# placa3.net
KiCad netlist of a schematic drawn in EAGLE
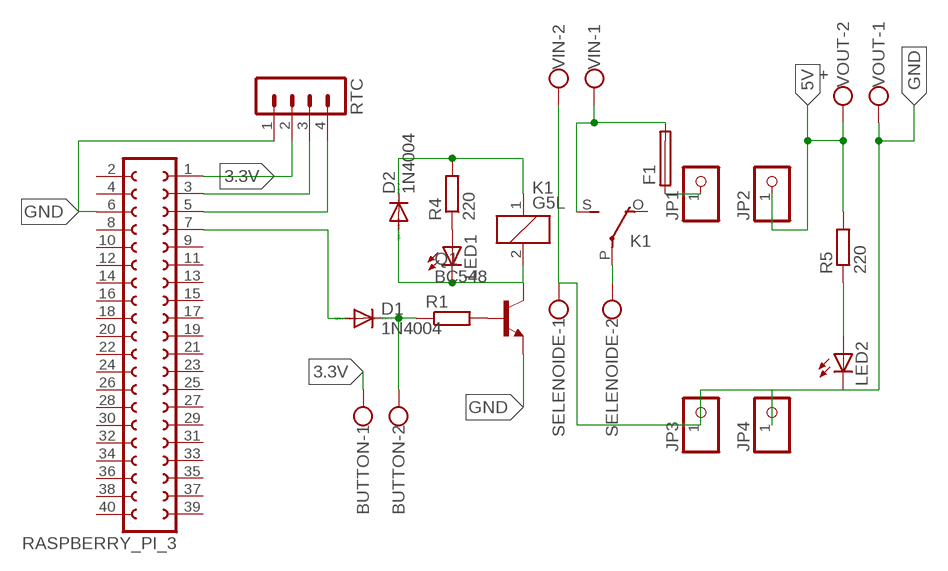
[diagram p0: schematic, sheet 1]

(export (version "E")
  (design (tool "Eeschema 10.0.6"))
  (components
    (comp (ref "BUTTON")
      (value "W237-102")
      (footprint "eagle-import:W237-102")
      (fields (field (name "MPN") "237-102"))
      (libsource (lib "eagle-import") (part "W237-102"))
    )
    (comp (ref "D1")
      (value "1N4004")
      (footprint "eagle-import:DO41-10")
      (libsource (lib "eagle-import") (part "1N4004"))
    )
    (comp (ref "D2")
      (value "1N4004")
      (footprint "eagle-import:DO41-10")
      (libsource (lib "eagle-import") (part "1N4004"))
    )
    (comp (ref "F1")
      (value "SH22,5")
      (footprint "eagle-import:SH22,5")
      (fields (field (name "MF") "SCHURTER") (field (name "MPN") "0031.8201"))
      (libsource (lib "eagle-import") (part "SH22,5"))
    )
    (comp (ref "JP1")
      (value "PINHD-1X1")
      (footprint "eagle-import:1X01")
      (libsource (lib "eagle-import") (part "PINHD-1X1"))
    )
    (comp (ref "JP2")
      (value "PINHD-1X1")
      (footprint "eagle-import:1X01")
      (libsource (lib "eagle-import") (part "PINHD-1X1"))
    )
    (comp (ref "JP3")
      (value "PINHD-1X1")
      (footprint "eagle-import:1X01")
      (libsource (lib "eagle-import") (part "PINHD-1X1"))
    )
    (comp (ref "JP4")
      (value "PINHD-1X1")
      (footprint "eagle-import:1X01")
      (libsource (lib "eagle-import") (part "PINHD-1X1"))
    )
    (comp (ref "K1")
      (value "G5L")
      (footprint "eagle-import:G5LE")
      (libsource (lib "eagle-import") (part "G5L"))
    )
    (comp (ref "LED1")
      (value "LED5MM")
      (footprint "eagle-import:LED5MM")
      (libsource (lib "eagle-import") (part "LED5MM"))
    )
    (comp (ref "LED2")
      (value "LED5MM")
      (footprint "eagle-import:LED5MM")
      (libsource (lib "eagle-import") (part "LED5MM"))
    )
    (comp (ref "Q1")
      (value "BC548")
      (footprint "eagle-import:TO92-EBC")
      (libsource (lib "eagle-import") (part "BC548"))
    )
    (comp (ref "R1")
      (value "R-EU_0204/7")
      (footprint "eagle-import:0204_7")
      (libsource (lib "eagle-import") (part "R-EU_0204/7"))
    )
    (comp (ref "R4")
      (value "220")
      (footprint "eagle-import:0204_7")
      (libsource (lib "eagle-import") (part "R-EU_0204/7"))
    )
    (comp (ref "R5")
      (value "220")
      (footprint "eagle-import:0204_7")
      (libsource (lib "eagle-import") (part "R-EU_0204/7"))
    )
    (comp (ref "RASPBERRY_PI_3")
      (value "FE20-2")
      (footprint "eagle-import:FE20-2")
      (libsource (lib "eagle-import") (part "FE20-2"))
    )
    (comp (ref "RTC")
      (value "MA04-1")
      (footprint "eagle-import:MA04-1")
      (libsource (lib "eagle-import") (part "MA04-1"))
    )
    (comp (ref "SELENOIDE")
      (value "W237-102")
      (footprint "eagle-import:W237-102")
      (fields (field (name "MPN") "237-102"))
      (libsource (lib "eagle-import") (part "W237-102"))
    )
    (comp (ref "VIN")
      (value "W237-102")
      (footprint "eagle-import:W237-102")
      (fields (field (name "MPN") "237-102"))
      (libsource (lib "eagle-import") (part "W237-102"))
    )
    (comp (ref "VOUT")
      (value "+")
      (footprint "eagle-import:W237-102")
      (fields (field (name "MPN") "237-102"))
      (libsource (lib "eagle-import") (part "W237-102"))
    )
  )
  (nets
    (net (code "1") (name "3.3V") (class "Default")
      (node (ref "BUTTON") (pin "1") (pinfunction "KL_1") (pintype "passive"))
      (node (ref "RASPBERRY_PI_3") (pin "1") (pinfunction "1_1") (pintype "passive"))
      (node (ref "RTC") (pin "2") (pinfunction "2_2") (pintype "passive"))
    )
    (net (code "2") (name "5V") (class "Default")
      (node (ref "D2") (pin "C") (pinfunction "C_C") (pintype "passive"))
      (node (ref "JP2") (pin "1") (pinfunction "1_1") (pintype "passive"))
      (node (ref "K1") (pin "1") (pinfunction "1_1") (pintype "passive"))
      (node (ref "R4") (pin "2") (pinfunction "2_2") (pintype "passive"))
      (node (ref "R5") (pin "2") (pinfunction "2_2") (pintype "passive"))
      (node (ref "VOUT") (pin "2") (pinfunction "KL_2") (pintype "passive"))
    )
    (net (code "3") (name "GND") (class "Default")
      (node (ref "JP3") (pin "1") (pinfunction "1_1") (pintype "passive"))
      (node (ref "JP4") (pin "1") (pinfunction "1_1") (pintype "passive"))
      (node (ref "LED2") (pin "K") (pinfunction "C_K") (pintype "passive"))
      (node (ref "Q1") (pin "E") (pinfunction "E_E") (pintype "passive"))
      (node (ref "RASPBERRY_PI_3") (pin "6") (pinfunction "6_6") (pintype "passive"))
      (node (ref "RTC") (pin "1") (pinfunction "1_1") (pintype "passive"))
      (node (ref "SELENOIDE") (pin "1") (pinfunction "KL_1") (pintype "passive"))
      (node (ref "VIN") (pin "2") (pinfunction "KL_2") (pintype "passive"))
      (node (ref "VOUT") (pin "1") (pinfunction "KL_1") (pintype "passive"))
    )
    (net (code "4") (name "Net-(BUTTONB-KL)") (class "Default")
      (node (ref "BUTTON") (pin "2") (pinfunction "KL_2") (pintype "passive"))
      (node (ref "D1") (pin "C") (pinfunction "C_C") (pintype "passive"))
      (node (ref "R1") (pin "1") (pinfunction "1_1") (pintype "passive"))
    )
    (net (code "5") (name "Net-(D1-PadA)") (class "Default")
      (node (ref "D1") (pin "A") (pinfunction "A_A") (pintype "passive"))
      (node (ref "RASPBERRY_PI_3") (pin "7") (pinfunction "7_7") (pintype "passive"))
    )
    (net (code "6") (name "Net-(F1-Pad1)") (class "Default")
      (node (ref "F1") (pin "1") (pinfunction "1_1") (pintype "passive"))
      (node (ref "JP1") (pin "1") (pinfunction "1_1") (pintype "passive"))
    )
    (net (code "7") (name "Net-(LED1-C)") (class "Default")
      (node (ref "D2") (pin "A") (pinfunction "A_A") (pintype "passive"))
      (node (ref "K1") (pin "2") (pinfunction "2_2") (pintype "passive"))
      (node (ref "LED1") (pin "K") (pinfunction "C_K") (pintype "passive"))
      (node (ref "Q1") (pin "C") (pinfunction "C_C") (pintype "passive"))
    )
    (net (code "8") (name "Net-(LED1-PadA)") (class "Default")
      (node (ref "LED1") (pin "A") (pinfunction "A_A") (pintype "passive"))
      (node (ref "R4") (pin "1") (pinfunction "1_1") (pintype "passive"))
    )
    (net (code "9") (name "Net-(LED2-PadA)") (class "Default")
      (node (ref "LED2") (pin "A") (pinfunction "A_A") (pintype "passive"))
      (node (ref "R5") (pin "1") (pinfunction "1_1") (pintype "passive"))
    )
    (net (code "10") (name "Net-(Q1-PadB)") (class "Default")
      (node (ref "Q1") (pin "B") (pinfunction "B_B") (pintype "passive"))
      (node (ref "R1") (pin "2") (pinfunction "2_2") (pintype "passive"))
    )
    (net (code "11") (name "Net-(RASPBERRY_PI_3-Pad3)") (class "Default")
      (node (ref "RASPBERRY_PI_3") (pin "3") (pinfunction "3_3") (pintype "passive"))
      (node (ref "RTC") (pin "3") (pinfunction "3_3") (pintype "passive"))
    )
    (net (code "12") (name "Net-(RASPBERRY_PI_3-Pad5)") (class "Default")
      (node (ref "RASPBERRY_PI_3") (pin "5") (pinfunction "5_5") (pintype "passive"))
      (node (ref "RTC") (pin "4") (pinfunction "4_4") (pintype "passive"))
    )
    (net (code "13") (name "Net-(SELENOIDEB-KL)") (class "Default")
      (node (ref "K1") (pin "P") (pinfunction "P_P") (pintype "passive"))
      (node (ref "SELENOIDE") (pin "2") (pinfunction "KL_2") (pintype "passive"))
    )
    (net (code "14") (name "Net-(VINA-KL)") (class "Default")
      (node (ref "F1") (pin "2") (pinfunction "2_2") (pintype "passive"))
      (node (ref "K1") (pin "S") (pinfunction "S_S") (pintype "passive"))
      (node (ref "VIN") (pin "1") (pinfunction "KL_1") (pintype "passive"))
    )
    (net (code "15") (name "unconnected-(K1-PadO)") (class "Default")
      (node (ref "K1") (pin "O") (pinfunction "O_O") (pintype "passive"))
    )
    (net (code "16") (name "unconnected-(RASPBERRY_PI_3-Pad2)") (class "Default")
      (node (ref "RASPBERRY_PI_3") (pin "2") (pinfunction "2_2") (pintype "passive"))
    )
    (net (code "17") (name "unconnected-(RASPBERRY_PI_3-Pad4)") (class "Default")
      (node (ref "RASPBERRY_PI_3") (pin "4") (pinfunction "4_4") (pintype "passive"))
    )
    (net (code "18") (name "unconnected-(RASPBERRY_PI_3-Pad8)") (class "Default")
      (node (ref "RASPBERRY_PI_3") (pin "8") (pinfunction "8_8") (pintype "passive"))
    )
    (net (code "19") (name "unconnected-(RASPBERRY_PI_3-Pad9)") (class "Default")
      (node (ref "RASPBERRY_PI_3") (pin "9") (pinfunction "9_9") (pintype "passive"))
    )
    (net (code "20") (name "unconnected-(RASPBERRY_PI_3-Pad10)") (class "Default")
      (node (ref "RASPBERRY_PI_3") (pin "10") (pinfunction "10_10") (pintype "passive"))
    )
    (net (code "21") (name "unconnected-(RASPBERRY_PI_3-Pad11)") (class "Default")
      (node (ref "RASPBERRY_PI_3") (pin "11") (pinfunction "11_11") (pintype "passive"))
    )
    (net (code "22") (name "unconnected-(RASPBERRY_PI_3-Pad12)") (class "Default")
      (node (ref "RASPBERRY_PI_3") (pin "12") (pinfunction "12_12") (pintype "passive"))
    )
    (net (code "23") (name "unconnected-(RASPBERRY_PI_3-Pad13)") (class "Default")
      (node (ref "RASPBERRY_PI_3") (pin "13") (pinfunction "13_13") (pintype "passive"))
    )
    (net (code "24") (name "unconnected-(RASPBERRY_PI_3-Pad14)") (class "Default")
      (node (ref "RASPBERRY_PI_3") (pin "14") (pinfunction "14_14") (pintype "passive"))
    )
    (net (code "25") (name "unconnected-(RASPBERRY_PI_3-Pad15)") (class "Default")
      (node (ref "RASPBERRY_PI_3") (pin "15") (pinfunction "15_15") (pintype "passive"))
    )
    (net (code "26") (name "unconnected-(RASPBERRY_PI_3-Pad16)") (class "Default")
      (node (ref "RASPBERRY_PI_3") (pin "16") (pinfunction "16_16") (pintype "passive"))
    )
    (net (code "27") (name "unconnected-(RASPBERRY_PI_3-Pad17)") (class "Default")
      (node (ref "RASPBERRY_PI_3") (pin "17") (pinfunction "17_17") (pintype "passive"))
    )
    (net (code "28") (name "unconnected-(RASPBERRY_PI_3-Pad18)") (class "Default")
      (node (ref "RASPBERRY_PI_3") (pin "18") (pinfunction "18_18") (pintype "passive"))
    )
    (net (code "29") (name "unconnected-(RASPBERRY_PI_3-Pad19)") (class "Default")
      (node (ref "RASPBERRY_PI_3") (pin "19") (pinfunction "19_19") (pintype "passive"))
    )
    (net (code "30") (name "unconnected-(RASPBERRY_PI_3-Pad20)") (class "Default")
      (node (ref "RASPBERRY_PI_3") (pin "20") (pinfunction "20_20") (pintype "passive"))
    )
    (net (code "31") (name "unconnected-(RASPBERRY_PI_3-Pad21)") (class "Default")
      (node (ref "RASPBERRY_PI_3") (pin "21") (pinfunction "21_21") (pintype "passive"))
    )
    (net (code "32") (name "unconnected-(RASPBERRY_PI_3-Pad22)") (class "Default")
      (node (ref "RASPBERRY_PI_3") (pin "22") (pinfunction "22_22") (pintype "passive"))
    )
    (net (code "33") (name "unconnected-(RASPBERRY_PI_3-Pad23)") (class "Default")
      (node (ref "RASPBERRY_PI_3") (pin "23") (pinfunction "23_23") (pintype "passive"))
    )
    (net (code "34") (name "unconnected-(RASPBERRY_PI_3-Pad24)") (class "Default")
      (node (ref "RASPBERRY_PI_3") (pin "24") (pinfunction "24_24") (pintype "passive"))
    )
    (net (code "35") (name "unconnected-(RASPBERRY_PI_3-Pad25)") (class "Default")
      (node (ref "RASPBERRY_PI_3") (pin "25") (pinfunction "25_25") (pintype "passive"))
    )
    (net (code "36") (name "unconnected-(RASPBERRY_PI_3-Pad26)") (class "Default")
      (node (ref "RASPBERRY_PI_3") (pin "26") (pinfunction "26_26") (pintype "passive"))
    )
    (net (code "37") (name "unconnected-(RASPBERRY_PI_3-Pad27)") (class "Default")
      (node (ref "RASPBERRY_PI_3") (pin "27") (pinfunction "27_27") (pintype "passive"))
    )
    (net (code "38") (name "unconnected-(RASPBERRY_PI_3-Pad28)") (class "Default")
      (node (ref "RASPBERRY_PI_3") (pin "28") (pinfunction "28_28") (pintype "passive"))
    )
    (net (code "39") (name "unconnected-(RASPBERRY_PI_3-Pad29)") (class "Default")
      (node (ref "RASPBERRY_PI_3") (pin "29") (pinfunction "29_29") (pintype "passive"))
    )
    (net (code "40") (name "unconnected-(RASPBERRY_PI_3-Pad30)") (class "Default")
      (node (ref "RASPBERRY_PI_3") (pin "30") (pinfunction "30_30") (pintype "passive"))
    )
    (net (code "41") (name "unconnected-(RASPBERRY_PI_3-Pad31)") (class "Default")
      (node (ref "RASPBERRY_PI_3") (pin "31") (pinfunction "31_31") (pintype "passive"))
    )
    (net (code "42") (name "unconnected-(RASPBERRY_PI_3-Pad32)") (class "Default")
      (node (ref "RASPBERRY_PI_3") (pin "32") (pinfunction "32_32") (pintype "passive"))
    )
    (net (code "43") (name "unconnected-(RASPBERRY_PI_3-Pad33)") (class "Default")
      (node (ref "RASPBERRY_PI_3") (pin "33") (pinfunction "33_33") (pintype "passive"))
    )
    (net (code "44") (name "unconnected-(RASPBERRY_PI_3-Pad34)") (class "Default")
      (node (ref "RASPBERRY_PI_3") (pin "34") (pinfunction "34_34") (pintype "passive"))
    )
    (net (code "45") (name "unconnected-(RASPBERRY_PI_3-Pad35)") (class "Default")
      (node (ref "RASPBERRY_PI_3") (pin "35") (pinfunction "35_35") (pintype "passive"))
    )
    (net (code "46") (name "unconnected-(RASPBERRY_PI_3-Pad36)") (class "Default")
      (node (ref "RASPBERRY_PI_3") (pin "36") (pinfunction "36_36") (pintype "passive"))
    )
    (net (code "47") (name "unconnected-(RASPBERRY_PI_3-Pad37)") (class "Default")
      (node (ref "RASPBERRY_PI_3") (pin "37") (pinfunction "37_37") (pintype "passive"))
    )
    (net (code "48") (name "unconnected-(RASPBERRY_PI_3-Pad38)") (class "Default")
      (node (ref "RASPBERRY_PI_3") (pin "38") (pinfunction "38_38") (pintype "passive"))
    )
    (net (code "49") (name "unconnected-(RASPBERRY_PI_3-Pad39)") (class "Default")
      (node (ref "RASPBERRY_PI_3") (pin "39") (pinfunction "39_39") (pintype "passive"))
    )
    (net (code "50") (name "unconnected-(RASPBERRY_PI_3-Pad40)") (class "Default")
      (node (ref "RASPBERRY_PI_3") (pin "40") (pinfunction "40_40") (pintype "passive"))
    )
  )
)
